# quadcopter.net
KiCad netlist of a schematic drawn in EAGLE
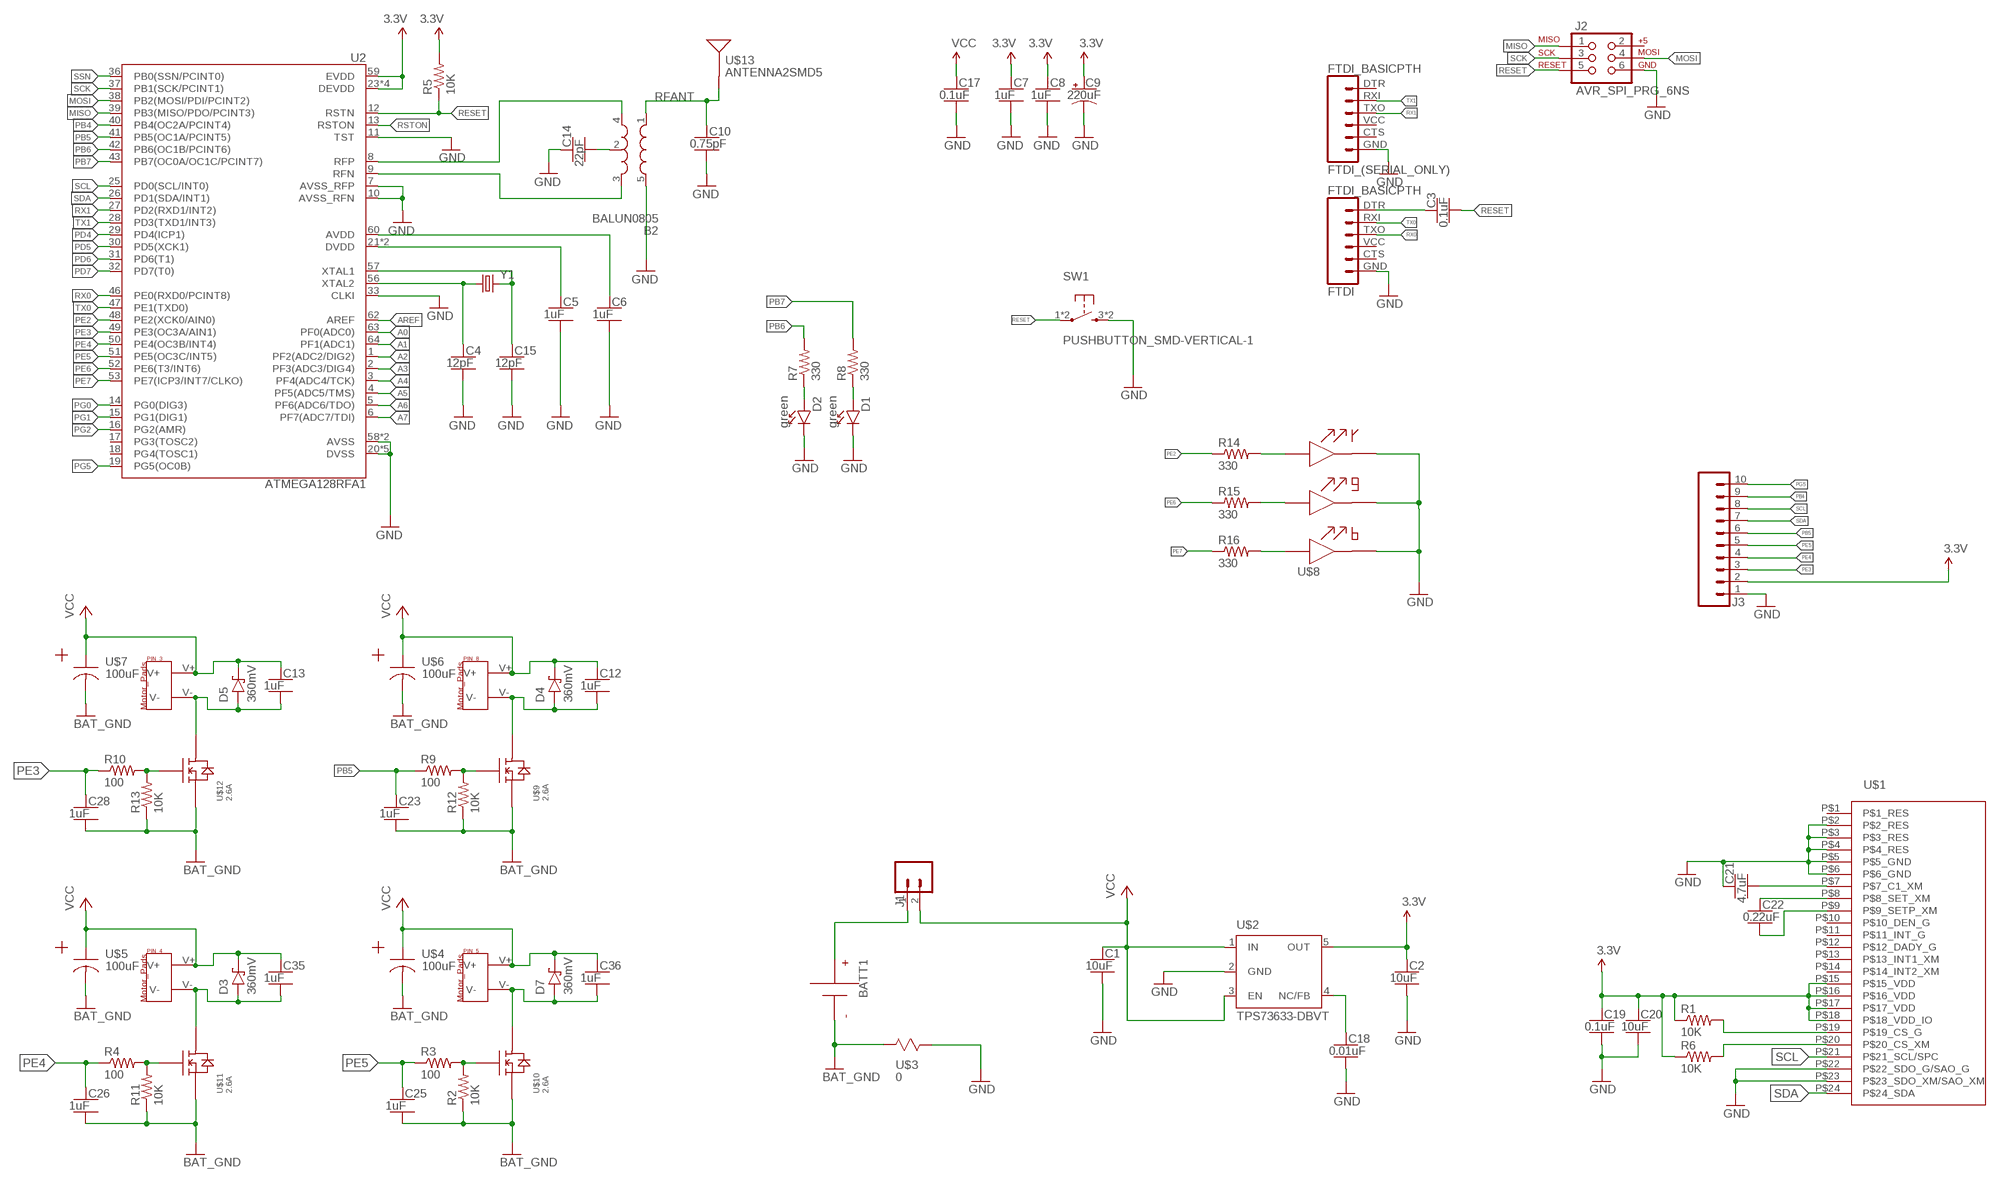
[diagram p0: schematic, sheet 1]

(export (version "E")
  (design (tool "Eeschema 10.0.6"))
  (components
    (comp (ref "B2")
      (value "BALUN0805")
      (footprint "eagle-import:BALUN")
      (fields (field (name "MFR") "Wurth Electronics Inc") (field (name "MPN") "748421245"))
      (libsource (lib "eagle-import") (part "BALUN0805"))
    )
    (comp (ref "BATT1")
      (value "BATTERY-HUBSAN-W/HOLDER")
      (footprint "eagle-import:BATTERY-W_HOLDER-380MAH-HUBSAN")
      (fields
        (field (name "MFR") "HUBSAN")
        (field (name "MPN") "X4-H107C-8-in-1")
        (field (name "CREATOR") "Swanson")
      )
      (libsource (lib "eagle-import") (part "BATTERY-HUBSAN-W/HOLDER"))
    )
    (comp (ref "C1")
      (value "10uF")
      (footprint "eagle-import:CAPC2012X140_HS")
      (fields
        (field (name "MFR") "Murata Electronics North America")
        (field (name "MPN") "GRM21BR61E106KA73L")
      )
      (libsource (lib "eagle-import") (part "CAPACITOR-NP_SMD-2012-0805_CERAMIC-10UF"))
    )
    (comp (ref "C2")
      (value "10uF")
      (footprint "eagle-import:CAPC2012X140_HS")
      (fields
        (field (name "MFR") "Murata Electronics North America")
        (field (name "MPN") "GRM21BR61E106KA73L")
      )
      (libsource (lib "eagle-import") (part "CAPACITOR-NP_SMD-2012-0805_CERAMIC-10UF"))
    )
    (comp (ref "C3")
      (value "0.1uF")
      (footprint "eagle-import:CAPC2012X140_HS")
      (fields
        (field (name "MFR") "Murata Electronics North America")
        (field (name "MPN") "GRM21BR71H104KA01L")
      )
      (libsource (lib "eagle-import") (part "CAPACITOR-NP_SMD-2012-0805_CERAMIC-0.1UF"))
    )
    (comp (ref "C4")
      (value "12pF")
      (footprint "eagle-import:CAPC2012X140_HS")
      (fields
        (field (name "MFR") "Murata Electronics North America")
        (field (name "MPN") "GRM21A5C2E120JW01D")
      )
      (libsource (lib "eagle-import") (part "CAPACITOR-NP_SMD-2012-0805_CERAMIC-12PF"))
    )
    (comp (ref "C5")
      (value "1uF")
      (footprint "eagle-import:CAPC2012X140_HS")
      (fields
        (field (name "MFR") "Murata Electronics North America")
        (field (name "MPN") "GRM21BR71H105KA12L")
      )
      (libsource (lib "eagle-import") (part "CAPACITOR-NP_SMD-2012-0805_CERAMIC-1UF"))
    )
    (comp (ref "C6")
      (value "1uF")
      (footprint "eagle-import:CAPC2012X140_HS")
      (fields
        (field (name "MFR") "Murata Electronics North America")
        (field (name "MPN") "GRM21BR71H105KA12L")
      )
      (libsource (lib "eagle-import") (part "CAPACITOR-NP_SMD-2012-0805_CERAMIC-1UF"))
    )
    (comp (ref "C7")
      (value "1uF")
      (footprint "eagle-import:CAPC2012X140_HS")
      (fields
        (field (name "MFR") "Murata Electronics North America")
        (field (name "MPN") "GRM21BR71H105KA12L")
      )
      (libsource (lib "eagle-import") (part "CAPACITOR-NP_SMD-2012-0805_CERAMIC-1UF"))
    )
    (comp (ref "C8")
      (value "1uF")
      (footprint "eagle-import:CAPC2012X140_HS")
      (fields
        (field (name "MFR") "Murata Electronics North America")
        (field (name "MPN") "GRM21BR71H105KA12L")
      )
      (libsource (lib "eagle-import") (part "CAPACITOR-NP_SMD-2012-0805_CERAMIC-1UF"))
    )
    (comp (ref "C9")
      (value "220uF")
      (footprint "eagle-import:CAPMP7343X310_HS")
      (fields (field (name "MFR") "AVX Corporation") (field (name "MPN") "TAJD227K006RNJ"))
      (libsource (lib "eagle-import") (part "CAPACITOR-POL_SMD-7043-D_TANTALUM-220UF"))
    )
    (comp (ref "C10")
      (value "0.75pF")
      (footprint "eagle-import:CAPC2012X140_HS")
      (fields
        (field (name "MFR") "Murata Electronics North America")
        (field (name "MPN") "GQM2195C2AR75CB01D")
      )
      (libsource (lib "eagle-import") (part "CAPACITOR-NP_SMD-2012-0805_CERAMIC-0.75PF"))
    )
    (comp (ref "C12")
      (value "1uF")
      (footprint "eagle-import:CAPC2012X140_HS")
      (fields
        (field (name "MFR") "Murata Electronics North America")
        (field (name "MPN") "GRM21BR71H105KA12L")
      )
      (libsource (lib "eagle-import") (part "CAPACITOR-NP_SMD-2012-0805_CERAMIC-1UF"))
    )
    (comp (ref "C13")
      (value "1uF")
      (footprint "eagle-import:CAPC2012X140_HS")
      (fields
        (field (name "MFR") "Murata Electronics North America")
        (field (name "MPN") "GRM21BR71H105KA12L")
      )
      (libsource (lib "eagle-import") (part "CAPACITOR-NP_SMD-2012-0805_CERAMIC-1UF"))
    )
    (comp (ref "C14")
      (value "22pF")
      (footprint "eagle-import:CAPC2012X140_HS")
      (fields
        (field (name "MFR") "Murata Electronics North America")
        (field (name "MPN") "GRM21A5C2E220JW01D")
      )
      (libsource (lib "eagle-import") (part "CAPACITOR-NP_SMD-2012-0805_CERAMIC-22PF"))
    )
    (comp (ref "C15")
      (value "12pF")
      (footprint "eagle-import:CAPC2012X140_HS")
      (fields
        (field (name "MFR") "Murata Electronics North America")
        (field (name "MPN") "GRM21A5C2E120JW01D")
      )
      (libsource (lib "eagle-import") (part "CAPACITOR-NP_SMD-2012-0805_CERAMIC-12PF"))
    )
    (comp (ref "C17")
      (value "0.1uF")
      (footprint "eagle-import:CAPC2012X140_HS")
      (fields
        (field (name "MFR") "Murata Electronics North America")
        (field (name "MPN") "GRM21BR71H104KA01L")
      )
      (libsource (lib "eagle-import") (part "CAPACITOR-NP_SMD-2012-0805_CERAMIC-0.1UF"))
    )
    (comp (ref "C18")
      (value "0.01uF")
      (footprint "eagle-import:CAPC2012X140_HS")
      (fields
        (field (name "MFR") "Murata Electronics North America")
        (field (name "MPN") "GRM2195C1H103FA01D")
      )
      (libsource (lib "eagle-import") (part "CAPACITOR-NP_SMD-2012-0805_CERAMIC-0.01UF"))
    )
    (comp (ref "C19")
      (value "0.1uF")
      (footprint "eagle-import:CAPC2012X140_HS")
      (fields
        (field (name "MFR") "Murata Electronics North America")
        (field (name "MPN") "GRM21BR71H104KA01L")
      )
      (libsource (lib "eagle-import") (part "CAPACITOR-NP_SMD-2012-0805_CERAMIC-0.1UF"))
    )
    (comp (ref "C20")
      (value "10uF")
      (footprint "eagle-import:CAPC2012X140_HS")
      (fields
        (field (name "MFR") "Murata Electronics North America")
        (field (name "MPN") "GRM21BR61E106KA73L")
      )
      (libsource (lib "eagle-import") (part "CAPACITOR-NP_SMD-2012-0805_CERAMIC-10UF"))
    )
    (comp (ref "C21")
      (value "4.7uF")
      (footprint "eagle-import:CAPC2012X140_HS")
      (fields
        (field (name "MFR") "Murata Electronics North America")
        (field (name "MPN") "GRM21BR61E475KA12L")
      )
      (libsource (lib "eagle-import") (part "CAPACITOR-NP_SMD-2012-0805_CERAMIC-4.7UF"))
    )
    (comp (ref "C22")
      (value "0.22uF")
      (footprint "eagle-import:CAPC2012X140_HS")
      (fields
        (field (name "MFR") "Murata Electronics North America")
        (field (name "MPN") "GRM21BR71H224KA01L")
      )
      (libsource (lib "eagle-import") (part "CAPACITOR-NP_SMD-2012-0805_CERAMIC-0.22UF"))
    )
    (comp (ref "C23")
      (value "1uF")
      (footprint "eagle-import:CAPC2012X140_HS")
      (fields
        (field (name "MFR") "Murata Electronics North America")
        (field (name "MPN") "GRM21BR71H105KA12L")
      )
      (libsource (lib "eagle-import") (part "CAPACITOR-NP_SMD-2012-0805_CERAMIC-1UF"))
    )
    (comp (ref "C25")
      (value "1uF")
      (footprint "eagle-import:CAPC2012X140_HS")
      (fields
        (field (name "MFR") "Murata Electronics North America")
        (field (name "MPN") "GRM21BR71H105KA12L")
      )
      (libsource (lib "eagle-import") (part "CAPACITOR-NP_SMD-2012-0805_CERAMIC-1UF"))
    )
    (comp (ref "C26")
      (value "1uF")
      (footprint "eagle-import:CAPC2012X140_HS")
      (fields
        (field (name "MFR") "Murata Electronics North America")
        (field (name "MPN") "GRM21BR71H105KA12L")
      )
      (libsource (lib "eagle-import") (part "CAPACITOR-NP_SMD-2012-0805_CERAMIC-1UF"))
    )
    (comp (ref "C28")
      (value "1uF")
      (footprint "eagle-import:CAPC2012X140_HS")
      (fields
        (field (name "MFR") "Murata Electronics North America")
        (field (name "MPN") "GRM21BR71H105KA12L")
      )
      (libsource (lib "eagle-import") (part "CAPACITOR-NP_SMD-2012-0805_CERAMIC-1UF"))
    )
    (comp (ref "C35")
      (value "1uF")
      (footprint "eagle-import:CAPC2012X140_HS")
      (fields
        (field (name "MFR") "Murata Electronics North America")
        (field (name "MPN") "GRM21BR71H105KA12L")
      )
      (libsource (lib "eagle-import") (part "CAPACITOR-NP_SMD-2012-0805_CERAMIC-1UF"))
    )
    (comp (ref "C36")
      (value "1uF")
      (footprint "eagle-import:CAPC2012X140_HS")
      (fields
        (field (name "MFR") "Murata Electronics North America")
        (field (name "MPN") "GRM21BR71H105KA12L")
      )
      (libsource (lib "eagle-import") (part "CAPACITOR-NP_SMD-2012-0805_CERAMIC-1UF"))
    )
    (comp (ref "D1")
      (value "green")
      (footprint "eagle-import:LEDSC125X200X120-2_HS")
      (fields (field (name "MFR") "Lite-On Inc") (field (name "MPN") "LTST-C170GKT"))
      (libsource (lib "eagle-import") (part "DIODE-LED_SMD-2012-0805-GREEN"))
    )
    (comp (ref "D2")
      (value "green")
      (footprint "eagle-import:LEDSC125X200X120-2_HS")
      (fields (field (name "MFR") "Lite-On Inc") (field (name "MPN") "LTST-C170GKT"))
      (libsource (lib "eagle-import") (part "DIODE-LED_SMD-2012-0805-GREEN"))
    )
    (comp (ref "D3")
      (value "360mV")
      (footprint "eagle-import:SOD3716X135_HS")
      (fields
        (field (name "MFR") "Toshiba Semiconductor and Storage")
        (field (name "MPN") "CRS08(TE85L,Q,M)")
      )
      (libsource (lib "eagle-import") (part "DIODE-SCHOTTKY_SMD-SOD123-360MV"))
    )
    (comp (ref "D4")
      (value "360mV")
      (footprint "eagle-import:SOD3716X135_HS")
      (fields
        (field (name "MFR") "Toshiba Semiconductor and Storage")
        (field (name "MPN") "CRS08(TE85L,Q,M)")
      )
      (libsource (lib "eagle-import") (part "DIODE-SCHOTTKY_SMD-SOD123-360MV"))
    )
    (comp (ref "D5")
      (value "360mV")
      (footprint "eagle-import:SOD3716X135_HS")
      (fields
        (field (name "MFR") "Toshiba Semiconductor and Storage")
        (field (name "MPN") "CRS08(TE85L,Q,M)")
      )
      (libsource (lib "eagle-import") (part "DIODE-SCHOTTKY_SMD-SOD123-360MV"))
    )
    (comp (ref "D7")
      (value "360mV")
      (footprint "eagle-import:SOD3716X135_HS")
      (fields
        (field (name "MFR") "Toshiba Semiconductor and Storage")
        (field (name "MPN") "CRS08(TE85L,Q,M)")
      )
      (libsource (lib "eagle-import") (part "DIODE-SCHOTTKY_SMD-SOD123-360MV"))
    )
    (comp (ref "FTDI")
      (value "FTDI_BASICPTH")
      (footprint "eagle-import:FTDI_BASIC")
      (fields (field (name "MFR") "Amphenol FCI") (field (name "MPN") "68016-406HLF"))
      (libsource (lib "eagle-import") (part "FTDI_BASICPTH"))
    )
    (comp (ref "FTDI_(SERIAL_ONLY)")
      (value "FTDI_BASICPTH")
      (footprint "eagle-import:FTDI_BASIC")
      (fields (field (name "MFR") "Amphenol FCI") (field (name "MPN") "68016-406HLF"))
      (libsource (lib "eagle-import") (part "FTDI_BASICPTH"))
    )
    (comp (ref "J1")
      (value "MALE_HEADER_2POS-2X1-0.1IN")
      (footprint "eagle-import:MALE_HEADER_2X1_0.1IN")
      (fields
        (field (name "MFR") "3M")
        (field (name "MPN") "961102-6404-AR")
        (field (name "CREATOR") "SWANSON")
      )
      (libsource (lib "eagle-import") (part "MALE_HEADER_2POS-2X1-0.1IN"))
    )
    (comp (ref "J2")
      (value "AVR_SPI_PRG_6NS")
      (footprint "eagle-import:2X3-NS")
      (fields (field (name "MFR") "Amphenol FCI") (field (name "MPN") "67997-206HLF"))
      (libsource (lib "eagle-import") (part "AVR_SPI_PRG_6NS"))
    )
    (comp (ref "J3")
      (value "SIP-10_TH-254X10-1")
      (footprint "eagle-import:HDRV10W63P254_10X1_2540X254H838_HS")
      (fields (field (name "MFR") "Amphenol FCI") (field (name "MPN") "68000-110HLF"))
      (libsource (lib "eagle-import") (part "SIP-10_TH-254X10-1"))
    )
    (comp (ref "PIN_3")
      (value "MOTOR_PADS")
      (footprint "eagle-import:MOTOR_PADS")
      (fields (field (name "MFR") "NA"))
      (libsource (lib "eagle-import") (part "MOTOR_PADS"))
    )
    (comp (ref "PIN_4")
      (value "MOTOR_PADS")
      (footprint "eagle-import:MOTOR_PADS")
      (fields (field (name "MFR") "NA"))
      (libsource (lib "eagle-import") (part "MOTOR_PADS"))
    )
    (comp (ref "PIN_5")
      (value "MOTOR_PADS")
      (footprint "eagle-import:MOTOR_PADS")
      (fields (field (name "MFR") "NA"))
      (libsource (lib "eagle-import") (part "MOTOR_PADS"))
    )
    (comp (ref "PIN_8")
      (value "MOTOR_PADS")
      (footprint "eagle-import:MOTOR_PADS")
      (fields (field (name "MFR") "NA"))
      (libsource (lib "eagle-import") (part "MOTOR_PADS"))
    )
    (comp (ref "R1")
      (value "10K")
      (footprint "eagle-import:RESC2012X60_HS")
      (fields (field (name "MFR") "Yageo") (field (name "MPN") "RC0805JR-0710KL"))
      (libsource (lib "eagle-import") (part "RESISTOR_SMD-2012-0805-10K"))
    )
    (comp (ref "R2")
      (value "10K")
      (footprint "eagle-import:RESC2012X60_HS")
      (fields (field (name "MFR") "Yageo") (field (name "MPN") "RC0805JR-0710KL"))
      (libsource (lib "eagle-import") (part "RESISTOR_SMD-2012-0805-10K"))
    )
    (comp (ref "R3")
      (value "100")
      (footprint "eagle-import:RESC2012X60_HS")
      (fields (field (name "MFR") "Yageo") (field (name "MPN") "RC0805JR-07100RL"))
      (libsource (lib "eagle-import") (part "RESISTOR_SMD-2012-0805-100"))
    )
    (comp (ref "R4")
      (value "100")
      (footprint "eagle-import:RESC2012X60_HS")
      (fields (field (name "MFR") "Yageo") (field (name "MPN") "RC0805JR-07100RL"))
      (libsource (lib "eagle-import") (part "RESISTOR_SMD-2012-0805-100"))
    )
    (comp (ref "R5")
      (value "10K")
      (footprint "eagle-import:RESC2012X60_HS")
      (fields (field (name "MFR") "Yageo") (field (name "MPN") "RC0805JR-0710KL"))
      (libsource (lib "eagle-import") (part "RESISTOR_SMD-2012-0805-10K"))
    )
    (comp (ref "R6")
      (value "10K")
      (footprint "eagle-import:RESC2012X60_HS")
      (fields (field (name "MFR") "Yageo") (field (name "MPN") "RC0805JR-0710KL"))
      (libsource (lib "eagle-import") (part "RESISTOR_SMD-2012-0805-10K"))
    )
    (comp (ref "R7")
      (value "330")
      (footprint "eagle-import:RESC2012X60_HS")
      (fields (field (name "MFR") "Yageo") (field (name "MPN") "RC0805JR-07330RL"))
      (libsource (lib "eagle-import") (part "RESISTOR_SMD-2012-0805-330"))
    )
    (comp (ref "R8")
      (value "330")
      (footprint "eagle-import:RESC2012X60_HS")
      (fields (field (name "MFR") "Yageo") (field (name "MPN") "RC0805JR-07330RL"))
      (libsource (lib "eagle-import") (part "RESISTOR_SMD-2012-0805-330"))
    )
    (comp (ref "R9")
      (value "100")
      (footprint "eagle-import:RESC2012X60_HS")
      (fields (field (name "MFR") "Yageo") (field (name "MPN") "RC0805JR-07100RL"))
      (libsource (lib "eagle-import") (part "RESISTOR_SMD-2012-0805-100"))
    )
    (comp (ref "R10")
      (value "100")
      (footprint "eagle-import:RESC2012X60_HS")
      (fields (field (name "MFR") "Yageo") (field (name "MPN") "RC0805JR-07100RL"))
      (libsource (lib "eagle-import") (part "RESISTOR_SMD-2012-0805-100"))
    )
    (comp (ref "R11")
      (value "10K")
      (footprint "eagle-import:RESC2012X60_HS")
      (fields (field (name "MFR") "Yageo") (field (name "MPN") "RC0805JR-0710KL"))
      (libsource (lib "eagle-import") (part "RESISTOR_SMD-2012-0805-10K"))
    )
    (comp (ref "R12")
      (value "10K")
      (footprint "eagle-import:RESC2012X60_HS")
      (fields (field (name "MFR") "Yageo") (field (name "MPN") "RC0805JR-0710KL"))
      (libsource (lib "eagle-import") (part "RESISTOR_SMD-2012-0805-10K"))
    )
    (comp (ref "R13")
      (value "10K")
      (footprint "eagle-import:RESC2012X60_HS")
      (fields (field (name "MFR") "Yageo") (field (name "MPN") "RC0805JR-0710KL"))
      (libsource (lib "eagle-import") (part "RESISTOR_SMD-2012-0805-10K"))
    )
    (comp (ref "R14")
      (value "330")
      (footprint "eagle-import:RESC2012X60_HS")
      (fields (field (name "MFR") "Yageo") (field (name "MPN") "RC0805JR-07330RL"))
      (libsource (lib "eagle-import") (part "RESISTOR_SMD-2012-0805-330"))
    )
    (comp (ref "R15")
      (value "330")
      (footprint "eagle-import:RESC2012X60_HS")
      (fields (field (name "MFR") "Yageo") (field (name "MPN") "RC0805JR-07330RL"))
      (libsource (lib "eagle-import") (part "RESISTOR_SMD-2012-0805-330"))
    )
    (comp (ref "R16")
      (value "330")
      (footprint "eagle-import:RESC2012X60_HS")
      (fields (field (name "MFR") "Yageo") (field (name "MPN") "RC0805JR-07330RL"))
      (libsource (lib "eagle-import") (part "RESISTOR_SMD-2012-0805-330"))
    )
    (comp (ref "SW1")
      (value "PUSHBUTTON_SMD-VERTICAL-1")
      (footprint "eagle-import:TE_FSM8JSMA_HS")
      (fields (field (name "MFR") "TE Connectivity Alcoswitch Switches") (field (name "MPN") "FSM4JSMA"))
      (libsource (lib "eagle-import") (part "PUSHBUTTON_SMD-VERTICAL-1"))
    )
    (comp (ref "U$1")
      (value "IMU")
      (footprint "eagle-import:LGA-24_4X4MM")
      (fields
        (field (name "MFR") "STMicroelectronics")
        (field (name "MPN") "LSM9DS0TR")
        (field (name "CREATOR") "Xuefei")
      )
      (libsource (lib "eagle-import") (part "IMU"))
    )
    (comp (ref "U$2")
      (value "TPS73633-DBVT")
      (footprint "eagle-import:SOT23-DBV")
      (fields (field (name "MFR") "Texas Instruments") (field (name "MPN") "LP3985IM5X-3.0/NOPB"))
      (libsource (lib "eagle-import") (part "TPS73633-DBVT"))
    )
    (comp (ref "U$3")
      (value "0")
      (footprint "eagle-import:SMD_RESISTOR")
      (fields
        (field (name "MFR") "Yageo")
        (field (name "MPN") "RC0805JR-070RL")
        (field (name "CREATOR") "Xuefei")
      )
      (libsource (lib "eagle-import") (part "RESISTOR"))
    )
    (comp (ref "U$4")
      (value "100uF")
      (footprint "eagle-import:TAJB_SMB_POLAR_CAP")
      (fields
        (field (name "MFR") "AVX Corporation")
        (field (name "MPN") "TAJB107K006RNJ")
        (field (name "CREATOR") "Xuefei")
      )
      (libsource (lib "eagle-import") (part "POLAR_CAP"))
    )
    (comp (ref "U$5")
      (value "100uF")
      (footprint "eagle-import:TAJB_SMB_POLAR_CAP")
      (fields
        (field (name "MFR") "AVX Corporation")
        (field (name "MPN") "TAJB107K006RNJ")
        (field (name "CREATOR") "Xuefei")
      )
      (libsource (lib "eagle-import") (part "POLAR_CAP"))
    )
    (comp (ref "U$6")
      (value "100uF")
      (footprint "eagle-import:TAJB_SMB_POLAR_CAP")
      (fields
        (field (name "MFR") "AVX Corporation")
        (field (name "MPN") "TAJB107K006RNJ")
        (field (name "CREATOR") "Xuefei")
      )
      (libsource (lib "eagle-import") (part "POLAR_CAP"))
    )
    (comp (ref "U$7")
      (value "100uF")
      (footprint "eagle-import:TAJB_SMB_POLAR_CAP")
      (fields
        (field (name "MFR") "AVX Corporation")
        (field (name "MPN") "TAJB107K006RNJ")
        (field (name "CREATOR") "Xuefei")
      )
      (libsource (lib "eagle-import") (part "POLAR_CAP"))
    )
    (comp (ref "U$8")
      (value "QBLP679E-RGB")
      (footprint "eagle-import:QBLP679E-RGB")
      (fields (field (name "MFR") "QT Brightek (QTB)") (field (name "CREATOR") "Xuefei"))
      (libsource (lib "eagle-import") (part "QBLP679E-RGB"))
    )
    (comp (ref "U$9")
      (value "2.6A")
      (footprint "eagle-import:LITTLE_FOOT_MOSFET_W__HEAT_SPREADER")
      (fields
        (field (name "MFR") "Vishay Siliconix")
        (field (name "MPN") "SI2302CDS-T1-E3")
        (field (name "CREATOR") "Xuefei")
      )
      (libsource (lib "eagle-import") (part "N-CHANNEL_MOSFETW/_HEAT_SINK"))
    )
    (comp (ref "U$10")
      (value "2.6A")
      (footprint "eagle-import:LITTLE_FOOT_MOSFET_W__HEAT_SPREADER")
      (fields
        (field (name "MFR") "Vishay Siliconix")
        (field (name "MPN") "SI2302CDS-T1-E3")
        (field (name "CREATOR") "Xuefei")
      )
      (libsource (lib "eagle-import") (part "N-CHANNEL_MOSFETW/_HEAT_SINK"))
    )
    (comp (ref "U$11")
      (value "2.6A")
      (footprint "eagle-import:LITTLE_FOOT_MOSFET_W__HEAT_SPREADER")
      (fields
        (field (name "MFR") "Vishay Siliconix")
        (field (name "MPN") "SI2302CDS-T1-E3")
        (field (name "CREATOR") "Xuefei")
      )
      (libsource (lib "eagle-import") (part "N-CHANNEL_MOSFETW/_HEAT_SINK"))
    )
    (comp (ref "U$12")
      (value "2.6A")
      (footprint "eagle-import:LITTLE_FOOT_MOSFET_W__HEAT_SPREADER")
      (fields
        (field (name "MFR") "Vishay Siliconix")
        (field (name "MPN") "SI2302CDS-T1-E3")
        (field (name "CREATOR") "Xuefei")
      )
      (libsource (lib "eagle-import") (part "N-CHANNEL_MOSFETW/_HEAT_SINK"))
    )
    (comp (ref "U$13")
      (value "ANTENNA2SMD5")
      (footprint "eagle-import:ANTENNA-CHIP5")
      (fields (field (name "MFR") "Linx Technologies Inc.") (field (name "MPN") "ANT-2.45-CHP-T"))
      (libsource (lib "eagle-import") (part "ANTENNA2SMD5"))
    )
    (comp (ref "U2")
      (value "ATMEGA128RFA1")
      (footprint "eagle-import:QFN-64")
      (fields (field (name "MFR") "Atmel") (field (name "MPN") "ATMEGA128RFA1-ZUR00"))
      (libsource (lib "eagle-import") (part "ATMEGA128RFA1"))
    )
    (comp (ref "Y1")
      (value "CRYSTAL5X3")
      (footprint "eagle-import:CRYSTAL-SMD-5X3")
      (fields (field (name "MFR") "Abracon LLC") (field (name "MPN") "ABM3B-16.000MHZ-B2-T"))
      (libsource (lib "eagle-import") (part "CRYSTAL5X3"))
    )
  )
  (nets
    (net (code "1") (name "/RFANT") (class "Default")
      (node (ref "B2") (pin "1") (pinfunction "IN_1") (pintype "bidirectional"))
      (node (ref "C10") (pin "1") (pinfunction "1_1") (pintype "passive"))
      (node (ref "U$13") (pin "FEED") (pinfunction "SIGNAL_FEED") (pintype "bidirectional"))
    )
    (net (code "2") (name "3.3V") (class "Default")
      (node (ref "C19") (pin "1") (pinfunction "1_1") (pintype "passive"))
      (node (ref "C2") (pin "1") (pinfunction "1_1") (pintype "passive"))
      (node (ref "C20") (pin "1") (pinfunction "1_1") (pintype "passive"))
      (node (ref "C7") (pin "1") (pinfunction "1_1") (pintype "passive"))
      (node (ref "C8") (pin "1") (pinfunction "1_1") (pintype "passive"))
      (node (ref "C9") (pin "1") (pinfunction "+_1") (pintype "passive"))
      (node (ref "J3") (pin "2") (pinfunction "2_2") (pintype "passive"))
      (node (ref "R1") (pin "1") (pinfunction "1_1") (pintype "passive"))
      (node (ref "R5") (pin "2") (pinfunction "2_2") (pintype "passive"))
      (node (ref "R6") (pin "1") (pinfunction "1_1") (pintype "passive"))
      (node (ref "U$1") (pin "P$15") (pinfunction "P$15_VDD_P$15") (pintype "bidirectional"))
      (node (ref "U$1") (pin "P$16") (pinfunction "P$16_VDD_P$16") (pintype "bidirectional"))
      (node (ref "U$1") (pin "P$17") (pinfunction "P$17_VDD_P$17") (pintype "bidirectional"))
      (node (ref "U$1") (pin "P$18") (pinfunction "P$18_VDD_IO_P$18") (pintype "bidirectional"))
      (node (ref "U$2") (pin "5") (pinfunction "OUT_5") (pintype "passive"))
      (node (ref "U2") (pin "23") (pinfunction "DEVDD_23") (pintype "bidirectional"))
      (node (ref "U2") (pin "34") (pinfunction "DEVDD_34") (pintype "bidirectional"))
      (node (ref "U2") (pin "44") (pinfunction "DEVDD_44") (pintype "bidirectional"))
      (node (ref "U2") (pin "54") (pinfunction "DEVDD_54") (pintype "bidirectional"))
      (node (ref "U2") (pin "59") (pinfunction "EVDD_59") (pintype "bidirectional"))
    )
    (net (code "3") (name "A0") (class "Default")
      (node (ref "U2") (pin "63") (pinfunction "PF0(ADC0)_63") (pintype "bidirectional"))
    )
    (net (code "4") (name "A1") (class "Default")
      (node (ref "U2") (pin "64") (pinfunction "PF1(ADC1)_64") (pintype "bidirectional"))
    )
    (net (code "5") (name "A2") (class "Default")
      (node (ref "U2") (pin "1") (pinfunction "PF2(ADC2/DIG2)_1") (pintype "bidirectional"))
    )
    (net (code "6") (name "A3") (class "Default")
      (node (ref "U2") (pin "2") (pinfunction "PF3(ADC3/DIG4)_2") (pintype "bidirectional"))
    )
    (net (code "7") (name "A4") (class "Default")
      (node (ref "U2") (pin "3") (pinfunction "PF4(ADC4/TCK)_3") (pintype "bidirectional"))
    )
    (net (code "8") (name "A5") (class "Default")
      (node (ref "U2") (pin "4") (pinfunction "PF5(ADC5/TMS)_4") (pintype "bidirectional"))
    )
    (net (code "9") (name "A6") (class "Default")
      (node (ref "U2") (pin "5") (pinfunction "PF6(ADC6/TDO)_5") (pintype "bidirectional"))
    )
    (net (code "10") (name "A7") (class "Default")
      (node (ref "U2") (pin "6") (pinfunction "PF7(ADC7/TDI)_6") (pintype "bidirectional"))
    )
    (net (code "11") (name "AREF") (class "Default")
      (node (ref "U2") (pin "62") (pinfunction "AREF_62") (pintype "bidirectional"))
    )
    (net (code "12") (name "BAT_GND") (class "Default")
      (node (ref "BATT1") (pin "-") (pinfunction "N_-") (pintype "bidirectional"))
      (node (ref "C23") (pin "2") (pinfunction "2_2") (pintype "passive"))
      (node (ref "C25") (pin "2") (pinfunction "2_2") (pintype "passive"))
      (node (ref "C26") (pin "2") (pinfunction "2_2") (pintype "passive"))
      (node (ref "C28") (pin "2") (pinfunction "2_2") (pintype "passive"))
      (node (ref "R11") (pin "1") (pinfunction "1_1") (pintype "passive"))
      (node (ref "R12") (pin "1") (pinfunction "1_1") (pintype "passive"))
      (node (ref "R13") (pin "1") (pinfunction "1_1") (pintype "passive"))
      (node (ref "R2") (pin "1") (pinfunction "1_1") (pintype "passive"))
      (node (ref "U$10") (pin "P$2") (pinfunction "P$2_S_P$2") (pintype "bidirectional"))
      (node (ref "U$11") (pin "P$2") (pinfunction "P$2_S_P$2") (pintype "bidirectional"))
      (node (ref "U$12") (pin "P$2") (pinfunction "P$2_S_P$2") (pintype "bidirectional"))
      (node (ref "U$3") (pin "P$1") (pinfunction "P$1_P$1") (pintype "bidirectional"))
      (node (ref "U$4") (pin "P$2") (pinfunction "2_P$2") (pintype "passive"))
      (node (ref "U$5") (pin "P$2") (pinfunction "2_P$2") (pintype "passive"))
      (node (ref "U$6") (pin "P$2") (pinfunction "2_P$2") (pintype "passive"))
      (node (ref "U$7") (pin "P$2") (pinfunction "2_P$2") (pintype "passive"))
      (node (ref "U$9") (pin "P$2") (pinfunction "P$2_S_P$2") (pintype "bidirectional"))
    )
    (net (code "13") (name "GND") (class "Default")
      (node (ref "B2") (pin "5") (pinfunction "GND_5") (pintype "bidirectional"))
      (node (ref "C1") (pin "2") (pinfunction "2_2") (pintype "passive"))
      (node (ref "C10") (pin "2") (pinfunction "2_2") (pintype "passive"))
      (node (ref "C14") (pin "1") (pinfunction "1_1") (pintype "passive"))
      (node (ref "C15") (pin "2") (pinfunction "2_2") (pintype "passive"))
      (node (ref "C17") (pin "2") (pinfunction "2_2") (pintype "passive"))
      (node (ref "C18") (pin "2") (pinfunction "2_2") (pintype "passive"))
      (node (ref "C19") (pin "2") (pinfunction "2_2") (pintype "passive"))
      (node (ref "C2") (pin "2") (pinfunction "2_2") (pintype "passive"))
      (node (ref "C20") (pin "2") (pinfunction "2_2") (pintype "passive"))
      (node (ref "C21") (pin "1") (pinfunction "1_1") (pintype "passive"))
      (node (ref "C4") (pin "2") (pinfunction "2_2") (pintype "passive"))
      (node (ref "C5") (pin "2") (pinfunction "2_2") (pintype "passive"))
      (node (ref "C6") (pin "2") (pinfunction "2_2") (pintype "passive"))
      (node (ref "C7") (pin "2") (pinfunction "2_2") (pintype "passive"))
      (node (ref "C8") (pin "2") (pinfunction "2_2") (pintype "passive"))
      (node (ref "C9") (pin "2") (pinfunction "-_2") (pintype "passive"))
      (node (ref "D1") (pin "C") (pinfunction "C_C") (pintype "passive"))
      (node (ref "D2") (pin "C") (pinfunction "C_C") (pintype "passive"))
      (node (ref "FTDI") (pin "GND") (pinfunction "6_GND") (pintype "passive"))
      (node (ref "FTDI_(SERIAL_ONLY)") (pin "GND") (pinfunction "6_GND") (pintype "passive"))
      (node (ref "J2") (pin "6") (pinfunction "6_6") (pintype "passive"))
      (node (ref "J3") (pin "1") (pinfunction "1_1") (pintype "passive"))
      (node (ref "SW1") (pin "3") (pinfunction "2_3") (pintype "passive"))
      (node (ref "SW1") (pin "4") (pinfunction "2_4") (pintype "passive"))
      (node (ref "U$1") (pin "P$2") (pinfunction "P$2_RES_P$2") (pintype "bidirectional"))
      (node (ref "U$1") (pin "P$22") (pinfunction "P$22_SDO_G/SAO_G_P$22") (pintype "bidirectional"))
      (node (ref "U$1") (pin "P$23") (pinfunction "P$23_SDO_XM/SAO_XM_P$23") (pintype "bidirectional"))
      (node (ref "U$1") (pin "P$3") (pinfunction "P$3_RES_P$3") (pintype "bidirectional"))
      (node (ref "U$1") (pin "P$4") (pinfunction "P$4_RES_P$4") (pintype "bidirectional"))
      (node (ref "U$1") (pin "P$5") (pinfunction "P$5_GND_P$5") (pintype "bidirectional"))
      (node (ref "U$1") (pin "P$6") (pinfunction "P$6_GND_P$6") (pintype "bidirectional"))
      (node (ref "U$2") (pin "2") (pinfunction "GND_2") (pintype "input"))
      (node (ref "U$3") (pin "P$2") (pinfunction "P$2_P$2") (pintype "bidirectional"))
      (node (ref "U$8") (pin "P$1") (pinfunction "P$1_P$1") (pintype "bidirectional"))
      (node (ref "U$8") (pin "P$2") (pinfunction "P$2_P$2") (pintype "bidirectional"))
      (node (ref "U$8") (pin "P$3") (pinfunction "P$3_P$3") (pintype "bidirectional"))
      (node (ref "U2") (pin "10") (pinfunction "AVSS_RFN_10") (pintype "bidirectional"))
      (node (ref "U2") (pin "11") (pinfunction "TST_11") (pintype "bidirectional"))
      (node (ref "U2") (pin "20") (pinfunction "DVSS_20") (pintype "bidirectional"))
      (node (ref "U2") (pin "24") (pinfunction "DVSS_24") (pintype "bidirectional"))
      (node (ref "U2") (pin "33") (pinfunction "CLKI_33") (pintype "bidirectional"))
      (node (ref "U2") (pin "35") (pinfunction "DVSS_35") (pintype "bidirectional"))
      (node (ref "U2") (pin "45") (pinfunction "DVSS_45") (pintype "bidirectional"))
      (node (ref "U2") (pin "55") (pinfunction "DVSS_55") (pintype "bidirectional"))
      (node (ref "U2") (pin "58") (pinfunction "AVSS_58") (pintype "bidirectional"))
      (node (ref "U2") (pin "61") (pinfunction "AVSS_61") (pintype "bidirectional"))
      (node (ref "U2") (pin "7") (pinfunction "AVSS_RFP_7") (pintype "bidirectional"))
    )
    (net (code "14") (name "MISO") (class "Default")
      (node (ref "J2") (pin "1") (pinfunction "1_1") (pintype "passive"))
      (node (ref "U2") (pin "39") (pinfunction "PB3(MISO/PDO/PCINT3)_39") (pintype "bidirectional"))
    )
    (net (code "15") (name "MOSI") (class "Default")
      (node (ref "J2") (pin "4") (pinfunction "4_4") (pintype "passive"))
      (node (ref "U2") (pin "38") (pinfunction "PB2(MOSI/PDI/PCINT2)_38") (pintype "bidirectional"))
    )
    (net (code "16") (name "Net-(B2-GND-Pad2)") (class "Default")
      (node (ref "B2") (pin "2") (pinfunction "GND_2") (pintype "bidirectional"))
      (node (ref "C14") (pin "2") (pinfunction "2_2") (pintype "passive"))
    )
    (net (code "17") (name "Net-(B2-OUT1)") (class "Default")
      (node (ref "B2") (pin "4") (pinfunction "OUT1_4") (pintype "bidirectional"))
      (node (ref "U2") (pin "8") (pinfunction "RFP_8") (pintype "bidirectional"))
    )
    (net (code "18") (name "Net-(B2-OUT2)") (class "Default")
      (node (ref "B2") (pin "3") (pinfunction "OUT2_3") (pintype "bidirectional"))
      (node (ref "U2") (pin "9") (pinfunction "RFN_9") (pintype "bidirectional"))
    )
    (net (code "19") (name "Net-(BATT1-P)") (class "Default")
      (node (ref "BATT1") (pin "+") (pinfunction "P_+") (pintype "bidirectional"))
      (node (ref "J1") (pin "1") (pinfunction "1_1") (pintype "passive"))
    )
    (net (code "20") (name "Net-(C5-Pad1)") (class "Default")
      (node (ref "C5") (pin "1") (pinfunction "1_1") (pintype "passive"))
      (node (ref "U2") (pin "21") (pinfunction "DVDD_21") (pintype "bidirectional"))
      (node (ref "U2") (pin "22") (pinfunction "DVDD_22") (pintype "bidirectional"))
    )
    (net (code "21") (name "Net-(D1-PadA)") (class "Default")
      (node (ref "D1") (pin "A") (pinfunction "A_A") (pintype "passive"))
      (node (ref "R8") (pin "1") (pinfunction "1_1") (pintype "passive"))
    )
    (net (code "22") (name "Net-(D2-PadA)") (class "Default")
      (node (ref "D2") (pin "A") (pinfunction "A_A") (pintype "passive"))
      (node (ref "R7") (pin "1") (pinfunction "1_1") (pintype "passive"))
    )
    (net (code "23") (name "Net-(FTDI-1)") (class "Default")
      (node (ref "C3") (pin "1") (pinfunction "1_1") (pintype "passive"))
      (node (ref "FTDI") (pin "DTR") (pinfunction "1_DTR") (pintype "passive"))
    )
    (net (code "24") (name "Net-(R14-Pad2)") (class "Default")
      (node (ref "R14") (pin "2") (pinfunction "2_2") (pintype "passive"))
      (node (ref "U$8") (pin "P$4") (pinfunction "P$4_P$4") (pintype "bidirectional"))
    )
    (net (code "25") (name "Net-(R15-Pad2)") (class "Default")
      (node (ref "R15") (pin "2") (pinfunction "2_2") (pintype "passive"))
      (node (ref "U$8") (pin "P$5") (pinfunction "P$5_P$5") (pintype "bidirectional"))
    )
    (net (code "26") (name "Net-(R16-Pad2)") (class "Default")
      (node (ref "R16") (pin "2") (pinfunction "2_2") (pintype "passive"))
      (node (ref "U$8") (pin "P$6") (pinfunction "P$6_P$6") (pintype "bidirectional"))
    )
    (net (code "27") (name "Net-(U$1-P$7_C1_XM)") (class "Default")
      (node (ref "C21") (pin "2") (pinfunction "2_2") (pintype "passive"))
      (node (ref "U$1") (pin "P$7") (pinfunction "P$7_C1_XM_P$7") (pintype "bidirectional"))
    )
    (net (code "28") (name "Net-(U$1-P$8_SET_XM)") (class "Default")
      (node (ref "C22") (pin "1") (pinfunction "1_1") (pintype "passive"))
      (node (ref "U$1") (pin "P$8") (pinfunction "P$8_SET_XM_P$8") (pintype "bidirectional"))
    )
    (net (code "29") (name "Net-(U$1-P$9_SETP_XM)") (class "Default")
      (node (ref "C22") (pin "2") (pinfunction "2_2") (pintype "passive"))
      (node (ref "U$1") (pin "P$9") (pinfunction "P$9_SETP_XM_P$9") (pintype "bidirectional"))
    )
    (net (code "30") (name "Net-(U$1-P$19_CS_G)") (class "Default")
      (node (ref "R1") (pin "2") (pinfunction "2_2") (pintype "passive"))
      (node (ref "U$1") (pin "P$19") (pinfunction "P$19_CS_G_P$19") (pintype "bidirectional"))
    )
    (net (code "31") (name "Net-(U$1-P$20_CS_XM)") (class "Default")
      (node (ref "R6") (pin "2") (pinfunction "2_2") (pintype "passive"))
      (node (ref "U$1") (pin "P$20") (pinfunction "P$20_CS_XM_P$20") (pintype "bidirectional"))
    )
    (net (code "32") (name "Net-(U$2-NC{slash}FB)") (class "Default")
      (node (ref "C18") (pin "1") (pinfunction "1_1") (pintype "passive"))
      (node (ref "U$2") (pin "4") (pinfunction "NC/FB_4") (pintype "passive"))
    )
    (net (code "33") (name "Net-(U$9-P$1_G)") (class "Default")
      (node (ref "R12") (pin "2") (pinfunction "2_2") (pintype "passive"))
      (node (ref "R9") (pin "2") (pinfunction "2_2") (pintype "passive"))
      (node (ref "U$9") (pin "P$1") (pinfunction "P$1_G_P$1") (pintype "bidirectional"))
    )
    (net (code "34") (name "Net-(U$9-P$3_D)") (class "Default")
      (node (ref "C12") (pin "2") (pinfunction "2_2") (pintype "passive"))
      (node (ref "D4") (pin "A") (pinfunction "A_A") (pintype "passive"))
      (node (ref "PIN_8") (pin "V-") (pinfunction "V-_V-") (pintype "bidirectional"))
      (node (ref "U$9") (pin "P$3") (pinfunction "P$3_D_P$3") (pintype "bidirectional"))
    )
    (net (code "35") (name "Net-(U$10-P$1_G)") (class "Default")
      (node (ref "R2") (pin "2") (pinfunction "2_2") (pintype "passive"))
      (node (ref "R3") (pin "2") (pinfunction "2_2") (pintype "passive"))
      (node (ref "U$10") (pin "P$1") (pinfunction "P$1_G_P$1") (pintype "bidirectional"))
    )
    (net (code "36") (name "Net-(U$10-P$3_D)") (class "Default")
      (node (ref "C36") (pin "2") (pinfunction "2_2") (pintype "passive"))
      (node (ref "D7") (pin "A") (pinfunction "A_A") (pintype "passive"))
      (node (ref "PIN_5") (pin "V-") (pinfunction "V-_V-") (pintype "bidirectional"))
      (node (ref "U$10") (pin "P$3") (pinfunction "P$3_D_P$3") (pintype "bidirectional"))
    )
    (net (code "37") (name "Net-(U$11-P$1_G)") (class "Default")
      (node (ref "R11") (pin "2") (pinfunction "2_2") (pintype "passive"))
      (node (ref "R4") (pin "2") (pinfunction "2_2") (pintype "passive"))
      (node (ref "U$11") (pin "P$1") (pinfunction "P$1_G_P$1") (pintype "bidirectional"))
    )
    (net (code "38") (name "Net-(U$11-P$3_D)") (class "Default")
      (node (ref "C35") (pin "2") (pinfunction "2_2") (pintype "passive"))
      (node (ref "D3") (pin "A") (pinfunction "A_A") (pintype "passive"))
      (node (ref "PIN_4") (pin "V-") (pinfunction "V-_V-") (pintype "bidirectional"))
      (node (ref "U$11") (pin "P$3") (pinfunction "P$3_D_P$3") (pintype "bidirectional"))
    )
    (net (code "39") (name "Net-(U$12-P$1_G)") (class "Default")
      (node (ref "R10") (pin "2") (pinfunction "2_2") (pintype "passive"))
      (node (ref "R13") (pin "2") (pinfunction "2_2") (pintype "passive"))
      (node (ref "U$12") (pin "P$1") (pinfunction "P$1_G_P$1") (pintype "bidirectional"))
    )
    (net (code "40") (name "Net-(U$12-P$3_D)") (class "Default")
      (node (ref "C13") (pin "2") (pinfunction "2_2") (pintype "passive"))
      (node (ref "D5") (pin "A") (pinfunction "A_A") (pintype "passive"))
      (node (ref "PIN_3") (pin "V-") (pinfunction "V-_V-") (pintype "bidirectional"))
      (node (ref "U$12") (pin "P$3") (pinfunction "P$3_D_P$3") (pintype "bidirectional"))
    )
    (net (code "41") (name "Net-(U2-AVDD)") (class "Default")
      (node (ref "C6") (pin "1") (pinfunction "1_1") (pintype "passive"))
      (node (ref "U2") (pin "60") (pinfunction "AVDD_60") (pintype "bidirectional"))
    )
    (net (code "42") (name "Net-(U2-XTAL1)") (class "Default")
      (node (ref "C15") (pin "1") (pinfunction "1_1") (pintype "passive"))
      (node (ref "U2") (pin "57") (pinfunction "XTAL1_57") (pintype "bidirectional"))
      (node (ref "Y1") (pin "3") (pinfunction "2_3") (pintype "passive"))
    )
    (net (code "43") (name "Net-(U2-XTAL2)") (class "Default")
      (node (ref "C4") (pin "1") (pinfunction "1_1") (pintype "passive"))
      (node (ref "U2") (pin "56") (pinfunction "XTAL2_56") (pintype "bidirectional"))
      (node (ref "Y1") (pin "1") (pinfunction "1_1") (pintype "passive"))
    )
    (net (code "44") (name "PB4") (class "Default")
      (node (ref "J3") (pin "9") (pinfunction "9_9") (pintype "passive"))
      (node (ref "U2") (pin "40") (pinfunction "PB4(OC2A/PCINT4)_40") (pintype "bidirectional"))
    )
    (net (code "45") (name "PB5") (class "Default")
      (node (ref "C23") (pin "1") (pinfunction "1_1") (pintype "passive"))
      (node (ref "J3") (pin "6") (pinfunction "6_6") (pintype "passive"))
      (node (ref "R9") (pin "1") (pinfunction "1_1") (pintype "passive"))
      (node (ref "U2") (pin "41") (pinfunction "PB5(OC1A/PCINT5)_41") (pintype "bidirectional"))
    )
    (net (code "46") (name "PB6") (class "Default")
      (node (ref "R7") (pin "2") (pinfunction "2_2") (pintype "passive"))
      (node (ref "U2") (pin "42") (pinfunction "PB6(OC1B/PCINT6)_42") (pintype "bidirectional"))
    )
    (net (code "47") (name "PB7") (class "Default")
      (node (ref "R8") (pin "2") (pinfunction "2_2") (pintype "passive"))
      (node (ref "U2") (pin "43") (pinfunction "PB7(OC0A/OC1C/PCINT7)_43") (pintype "bidirectional"))
    )
    (net (code "48") (name "PD4") (class "Default")
      (node (ref "U2") (pin "29") (pinfunction "PD4(ICP1)_29") (pintype "bidirectional"))
    )
    (net (code "49") (name "PD5") (class "Default")
      (node (ref "U2") (pin "30") (pinfunction "PD5(XCK1)_30") (pintype "bidirectional"))
    )
    (net (code "50") (name "PD6") (class "Default")
      (node (ref "U2") (pin "31") (pinfunction "PD6(T1)_31") (pintype "bidirectional"))
    )
    (net (code "51") (name "PD7") (class "Default")
      (node (ref "U2") (pin "32") (pinfunction "PD7(T0)_32") (pintype "bidirectional"))
    )
    (net (code "52") (name "PE2") (class "Default")
      (node (ref "R14") (pin "1") (pinfunction "1_1") (pintype "passive"))
      (node (ref "U2") (pin "48") (pinfunction "PE2(XCK0/AIN0)_48") (pintype "bidirectional"))
    )
    (net (code "53") (name "PE3") (class "Default")
      (node (ref "C28") (pin "1") (pinfunction "1_1") (pintype "passive"))
      (node (ref "J3") (pin "3") (pinfunction "3_3") (pintype "passive"))
      (node (ref "R10") (pin "1") (pinfunction "1_1") (pintype "passive"))
      (node (ref "U2") (pin "49") (pinfunction "PE3(OC3A/AIN1)_49") (pintype "bidirectional"))
    )
    (net (code "54") (name "PE4") (class "Default")
      (node (ref "C26") (pin "1") (pinfunction "1_1") (pintype "passive"))
      (node (ref "J3") (pin "4") (pinfunction "4_4") (pintype "passive"))
      (node (ref "R4") (pin "1") (pinfunction "1_1") (pintype "passive"))
      (node (ref "U2") (pin "50") (pinfunction "PE4(OC3B/INT4)_50") (pintype "bidirectional"))
    )
    (net (code "55") (name "PE5") (class "Default")
      (node (ref "C25") (pin "1") (pinfunction "1_1") (pintype "passive"))
      (node (ref "J3") (pin "5") (pinfunction "5_5") (pintype "passive"))
      (node (ref "R3") (pin "1") (pinfunction "1_1") (pintype "passive"))
      (node (ref "U2") (pin "51") (pinfunction "PE5(OC3C/INT5)_51") (pintype "bidirectional"))
    )
    (net (code "56") (name "PE6") (class "Default")
      (node (ref "R15") (pin "1") (pinfunction "1_1") (pintype "passive"))
      (node (ref "U2") (pin "52") (pinfunction "PE6(T3/INT6)_52") (pintype "bidirectional"))
    )
    (net (code "57") (name "PE7") (class "Default")
      (node (ref "R16") (pin "1") (pinfunction "1_1") (pintype "passive"))
      (node (ref "U2") (pin "53") (pinfunction "PE7(ICP3/INT7/CLKO)_53") (pintype "bidirectional"))
    )
    (net (code "58") (name "PG0") (class "Default")
      (node (ref "U2") (pin "14") (pinfunction "PG0(DIG3)_14") (pintype "bidirectional"))
    )
    (net (code "59") (name "PG1") (class "Default")
      (node (ref "U2") (pin "15") (pinfunction "PG1(DIG1)_15") (pintype "bidirectional"))
    )
    (net (code "60") (name "PG2") (class "Default")
      (node (ref "U2") (pin "16") (pinfunction "PG2(AMR)_16") (pintype "bidirectional"))
    )
    (net (code "61") (name "PG5") (class "Default")
      (node (ref "J3") (pin "10") (pinfunction "10_10") (pintype "passive"))
      (node (ref "U2") (pin "19") (pinfunction "PG5(OC0B)_19") (pintype "bidirectional"))
    )
    (net (code "62") (name "RESET") (class "Default")
      (node (ref "C3") (pin "2") (pinfunction "2_2") (pintype "passive"))
      (node (ref "J2") (pin "5") (pinfunction "5_5") (pintype "passive"))
      (node (ref "R5") (pin "1") (pinfunction "1_1") (pintype "passive"))
      (node (ref "SW1") (pin "1") (pinfunction "1_1") (pintype "passive"))
      (node (ref "SW1") (pin "2") (pinfunction "1_2") (pintype "passive"))
      (node (ref "U2") (pin "12") (pinfunction "RSTN_12") (pintype "bidirectional"))
    )
    (net (code "63") (name "RSTON") (class "Default")
      (node (ref "U2") (pin "13") (pinfunction "RSTON_13") (pintype "bidirectional"))
    )
    (net (code "64") (name "RX0") (class "Default")
      (node (ref "FTDI") (pin "TXO") (pinfunction "3_TXO") (pintype "passive"))
      (node (ref "U2") (pin "46") (pinfunction "PE0(RXD0/PCINT8)_46") (pintype "bidirectional"))
    )
    (net (code "65") (name "RX1") (class "Default")
      (node (ref "FTDI_(SERIAL_ONLY)") (pin "TXO") (pinfunction "3_TXO") (pintype "passive"))
      (node (ref "U2") (pin "27") (pinfunction "PD2(RXD1/INT2)_27") (pintype "bidirectional"))
    )
    (net (code "66") (name "SCK") (class "Default")
      (node (ref "J2") (pin "3") (pinfunction "3_3") (pintype "passive"))
      (node (ref "U2") (pin "37") (pinfunction "PB1(SCK/PCINT1)_37") (pintype "bidirectional"))
    )
    (net (code "67") (name "SCL") (class "Default")
      (node (ref "J3") (pin "8") (pinfunction "8_8") (pintype "passive"))
      (node (ref "U$1") (pin "P$21") (pinfunction "P$21_SCL/SPC_P$21") (pintype "bidirectional"))
      (node (ref "U2") (pin "25") (pinfunction "PD0(SCL/INT0)_25") (pintype "bidirectional"))
    )
    (net (code "68") (name "SDA") (class "Default")
      (node (ref "J3") (pin "7") (pinfunction "7_7") (pintype "passive"))
      (node (ref "U$1") (pin "P$24") (pinfunction "P$24_SDA_P$24") (pintype "bidirectional"))
      (node (ref "U2") (pin "26") (pinfunction "PD1(SDA/INT1)_26") (pintype "bidirectional"))
    )
    (net (code "69") (name "SSN") (class "Default")
      (node (ref "U2") (pin "36") (pinfunction "PB0(SSN/PCINT0)_36") (pintype "bidirectional"))
    )
    (net (code "70") (name "TX0") (class "Default")
      (node (ref "FTDI") (pin "RXI") (pinfunction "2_RXI") (pintype "passive"))
      (node (ref "U2") (pin "47") (pinfunction "PE1(TXD0)_47") (pintype "bidirectional"))
    )
    (net (code "71") (name "TX1") (class "Default")
      (node (ref "FTDI_(SERIAL_ONLY)") (pin "RXI") (pinfunction "2_RXI") (pintype "passive"))
      (node (ref "U2") (pin "28") (pinfunction "PD3(TXD1/INT3)_28") (pintype "bidirectional"))
    )
    (net (code "72") (name "VCC") (class "Default")
      (node (ref "C1") (pin "1") (pinfunction "1_1") (pintype "passive"))
      (node (ref "C12") (pin "1") (pinfunction "1_1") (pintype "passive"))
      (node (ref "C13") (pin "1") (pinfunction "1_1") (pintype "passive"))
      (node (ref "C17") (pin "1") (pinfunction "1_1") (pintype "passive"))
      (node (ref "C35") (pin "1") (pinfunction "1_1") (pintype "passive"))
      (node (ref "C36") (pin "1") (pinfunction "1_1") (pintype "passive"))
      (node (ref "D3") (pin "C") (pinfunction "C_C") (pintype "passive"))
      (node (ref "D4") (pin "C") (pinfunction "C_C") (pintype "passive"))
      (node (ref "D5") (pin "C") (pinfunction "C_C") (pintype "passive"))
      (node (ref "D7") (pin "C") (pinfunction "C_C") (pintype "passive"))
      (node (ref "J1") (pin "2") (pinfunction "2_2") (pintype "passive"))
      (node (ref "PIN_3") (pin "V+") (pinfunction "V+_V+") (pintype "bidirectional"))
      (node (ref "PIN_4") (pin "V+") (pinfunction "V+_V+") (pintype "bidirectional"))
      (node (ref "PIN_5") (pin "V+") (pinfunction "V+_V+") (pintype "bidirectional"))
      (node (ref "PIN_8") (pin "V+") (pinfunction "V+_V+") (pintype "bidirectional"))
      (node (ref "U$2") (pin "1") (pinfunction "IN_1") (pintype "input"))
      (node (ref "U$2") (pin "3") (pinfunction "EN_3") (pintype "input"))
      (node (ref "U$4") (pin "P$1") (pinfunction "1_P$1") (pintype "passive"))
      (node (ref "U$5") (pin "P$1") (pinfunction "1_P$1") (pintype "passive"))
      (node (ref "U$6") (pin "P$1") (pinfunction "1_P$1") (pintype "passive"))
      (node (ref "U$7") (pin "P$1") (pinfunction "1_P$1") (pintype "passive"))
    )
    (net (code "73") (name "unconnected-(FTDI-4-PadVCC)") (class "Default")
      (node (ref "FTDI") (pin "VCC") (pinfunction "4_VCC") (pintype "passive"))
    )
    (net (code "74") (name "unconnected-(FTDI-5-PadCTS)") (class "Default")
      (node (ref "FTDI") (pin "CTS") (pinfunction "5_CTS") (pintype "passive"))
    )
    (net (code "75") (name "unconnected-(FTDI_(SERIAL_ONLY)-1-PadDTR)") (class "Default")
      (node (ref "FTDI_(SERIAL_ONLY)") (pin "DTR") (pinfunction "1_DTR") (pintype "passive"))
    )
    (net (code "76") (name "unconnected-(FTDI_(SERIAL_ONLY)-4-PadVCC)") (class "Default")
      (node (ref "FTDI_(SERIAL_ONLY)") (pin "VCC") (pinfunction "4_VCC") (pintype "passive"))
    )
    (net (code "77") (name "unconnected-(FTDI_(SERIAL_ONLY)-5-PadCTS)") (class "Default")
      (node (ref "FTDI_(SERIAL_ONLY)") (pin "CTS") (pinfunction "5_CTS") (pintype "passive"))
    )
    (net (code "78") (name "unconnected-(J2-Pad2)") (class "Default")
      (node (ref "J2") (pin "2") (pinfunction "2_2") (pintype "passive"))
    )
    (net (code "79") (name "unconnected-(U$1-P$1_RES-PadP$1)") (class "Default")
      (node (ref "U$1") (pin "P$1") (pinfunction "P$1_RES_P$1") (pintype "bidirectional"))
    )
    (net (code "80") (name "unconnected-(U$1-P$10_DEN_G-PadP$10)") (class "Default")
      (node (ref "U$1") (pin "P$10") (pinfunction "P$10_DEN_G_P$10") (pintype "bidirectional"))
    )
    (net (code "81") (name "unconnected-(U$1-P$11_INT_G-PadP$11)") (class "Default")
      (node (ref "U$1") (pin "P$11") (pinfunction "P$11_INT_G_P$11") (pintype "bidirectional"))
    )
    (net (code "82") (name "unconnected-(U$1-P$12_DADY_G-PadP$12)") (class "Default")
      (node (ref "U$1") (pin "P$12") (pinfunction "P$12_DADY_G_P$12") (pintype "bidirectional"))
    )
    (net (code "83") (name "unconnected-(U$1-P$13_INT1_XM-PadP$13)") (class "Default")
      (node (ref "U$1") (pin "P$13") (pinfunction "P$13_INT1_XM_P$13") (pintype "bidirectional"))
    )
    (net (code "84") (name "unconnected-(U$1-P$14_INT2_XM-PadP$14)") (class "Default")
      (node (ref "U$1") (pin "P$14") (pinfunction "P$14_INT2_XM_P$14") (pintype "bidirectional"))
    )
    (net (code "85") (name "unconnected-(U2-PG3(TOSC2)-Pad17)") (class "Default")
      (node (ref "U2") (pin "17") (pinfunction "PG3(TOSC2)_17") (pintype "bidirectional"))
    )
    (net (code "86") (name "unconnected-(U2-PG4(TOSC1)-Pad18)") (class "Default")
      (node (ref "U2") (pin "18") (pinfunction "PG4(TOSC1)_18") (pintype "bidirectional"))
    )
  )
)
